# ch.net
KiCad netlist of a schematic drawn in Altium Designer
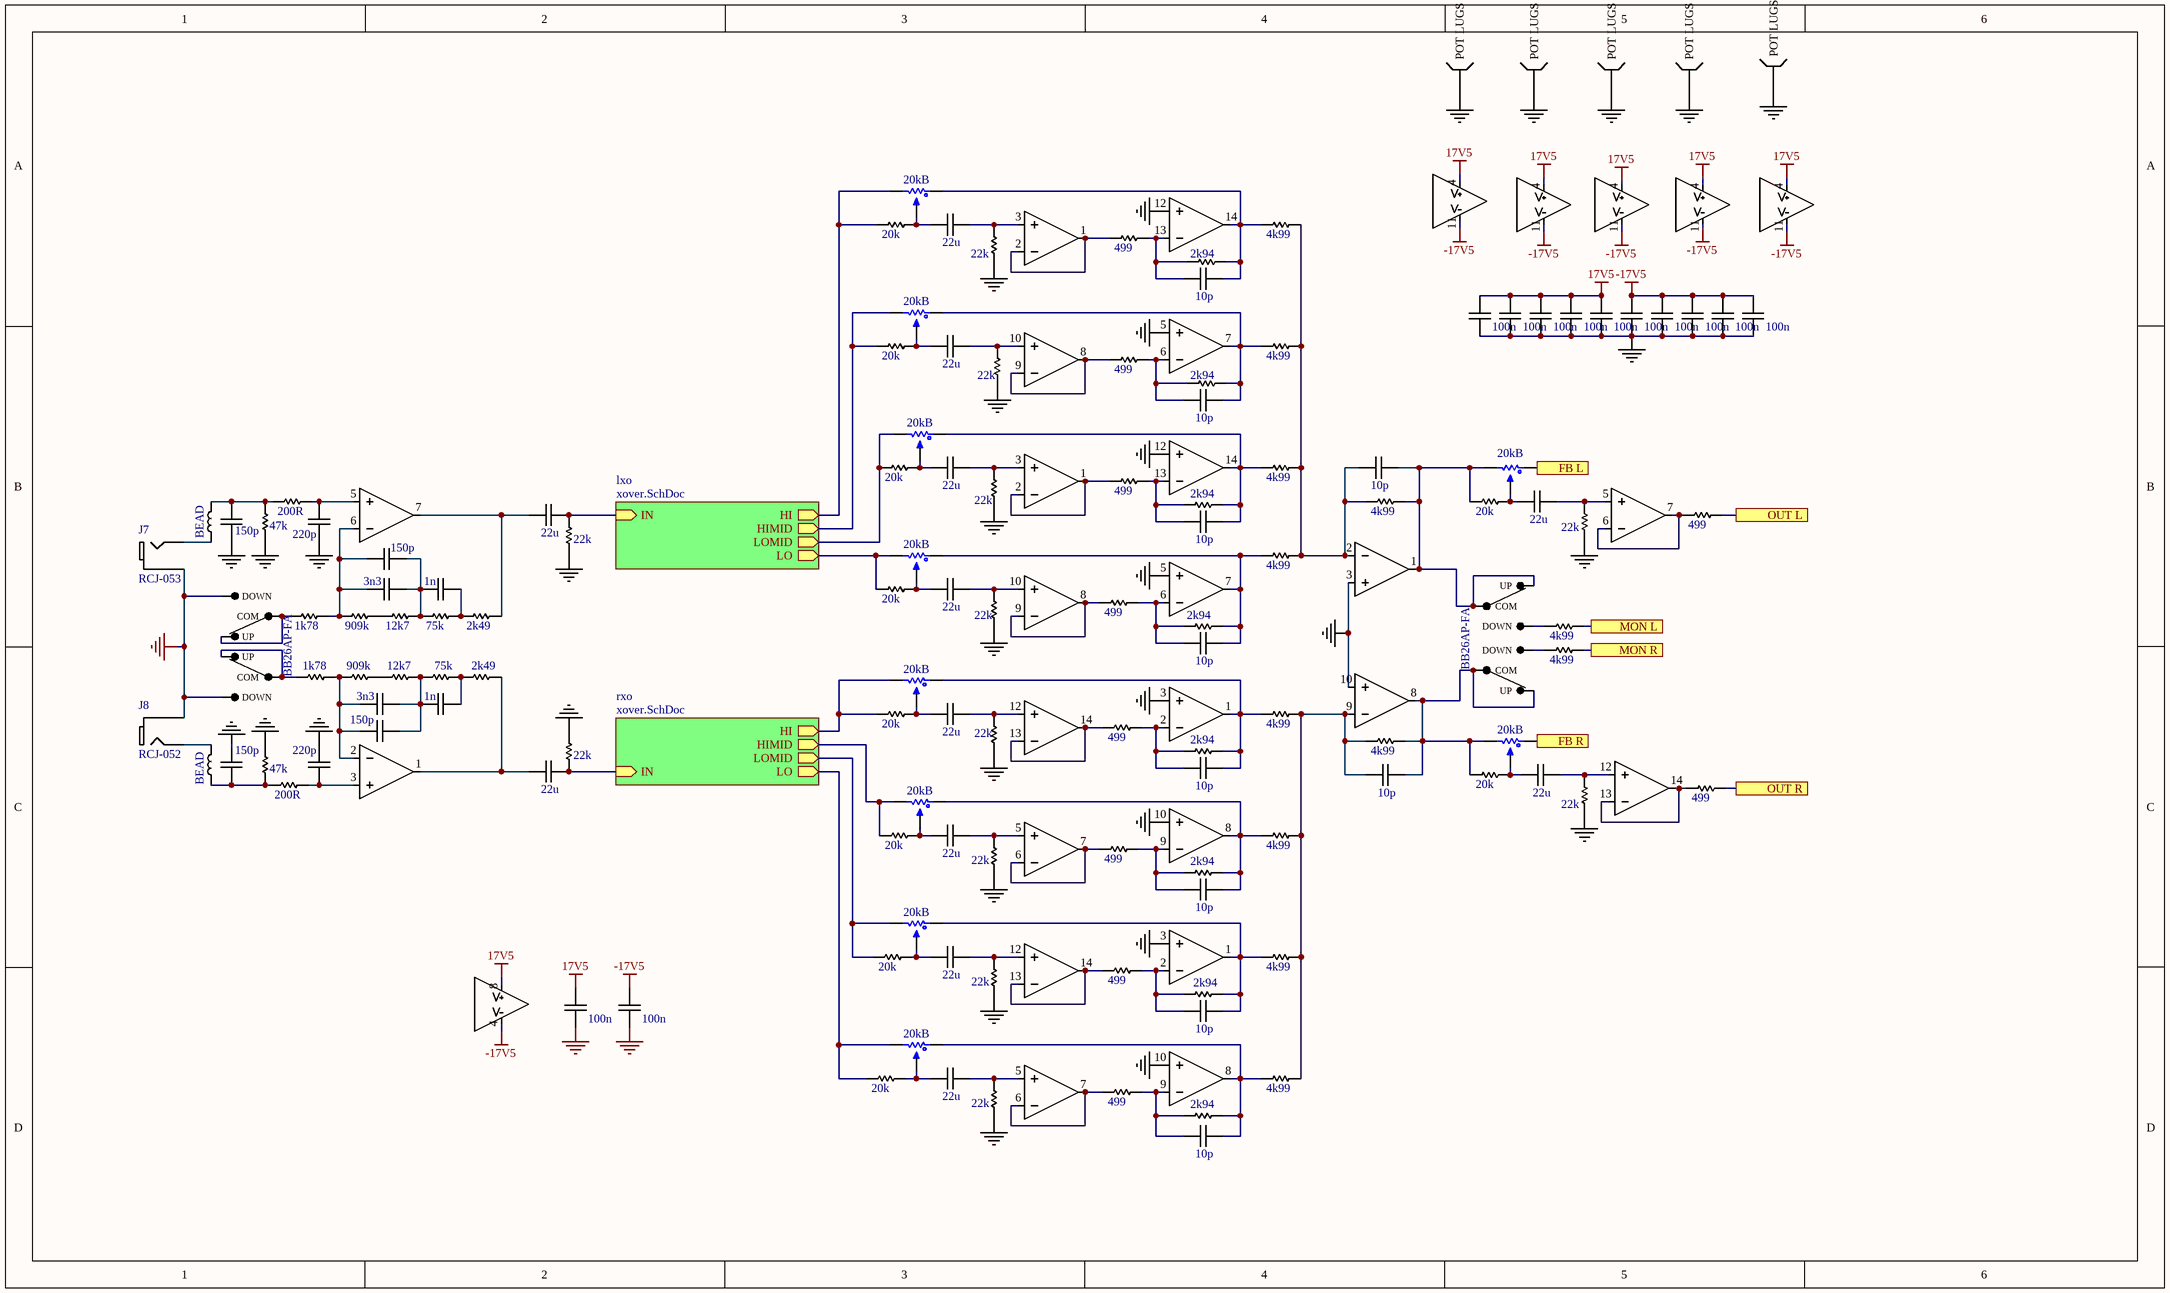
[diagram p0: ch.SchDoc]

(export (version "E")
  (design (tool "Eeschema 10.0.6"))
  (components
    (comp (ref "C1")
      (value "22u")
      (footprint "0805")
      (fields (field (name "PARTNUMBER") "GRT21BR61E226ME13L"))
      (libsource (lib "mix") (part "CAP"))
    )
    (comp (ref "C2")
      (value "10p")
      (footprint "0805")
      (fields (field (name "PARTNUMBER") "CC0805JRNPO9BN100"))
      (libsource (lib "mix") (part "CAP"))
    )
    (comp (ref "C3")
      (value "100n")
      (footprint "0805")
      (fields (field (name "PARTNUMBER") "C0805C104K1RAC7800"))
      (libsource (lib "mix") (part "CAP"))
    )
    (comp (ref "C4")
      (value "100n")
      (footprint "0805")
      (fields (field (name "PARTNUMBER") "C0805C104K1RAC7800"))
      (libsource (lib "mix") (part "CAP"))
    )
    (comp (ref "C6")
      (value "100n")
      (footprint "0805")
      (fields (field (name "PARTNUMBER") "C0805C104K1RAC7800"))
      (libsource (lib "mix") (part "CAP"))
    )
    (comp (ref "C8")
      (value "100n")
      (footprint "0805")
      (fields (field (name "PARTNUMBER") "C0805C104K1RAC7800"))
      (libsource (lib "mix") (part "CAP"))
    )
    (comp (ref "C9")
      (value "100n")
      (footprint "0805")
      (fields (field (name "PARTNUMBER") "C0805C104K1RAC7800"))
      (libsource (lib "mix") (part "CAP"))
    )
    (comp (ref "C10")
      (value "22u")
      (footprint "0805")
      (fields (field (name "PARTNUMBER") "GRT21BR61E226ME13L"))
      (libsource (lib "mix") (part "CAP"))
    )
    (comp (ref "C11")
      (value "10p")
      (footprint "0805")
      (fields (field (name "PARTNUMBER") "CC0805JRNPO9BN100"))
      (libsource (lib "mix") (part "CAP"))
    )
    (comp (ref "C12")
      (value "100n")
      (footprint "0805")
      (fields (field (name "PARTNUMBER") "C0805C104K1RAC7800"))
      (libsource (lib "mix") (part "CAP"))
    )
    (comp (ref "C13")
      (value "22u")
      (footprint "0805")
      (fields (field (name "PARTNUMBER") "GRT21BR61E226ME13L"))
      (libsource (lib "mix") (part "CAP"))
    )
    (comp (ref "C14")
      (value "22u")
      (footprint "0805")
      (fields (field (name "PARTNUMBER") "GRT21BR61E226ME13L"))
      (libsource (lib "mix") (part "CAP"))
    )
    (comp (ref "C16")
      (value "10p")
      (footprint "0805")
      (fields (field (name "PARTNUMBER") "CC0805JRNPO9BN100"))
      (libsource (lib "mix") (part "CAP"))
    )
    (comp (ref "C18")
      (value "22u")
      (footprint "0805")
      (fields (field (name "PARTNUMBER") "GRT21BR61E226ME13L"))
      (libsource (lib "mix") (part "CAP"))
    )
    (comp (ref "C19")
      (value "10p")
      (footprint "0805")
      (fields (field (name "PARTNUMBER") "CC0805JRNPO9BN100"))
      (libsource (lib "mix") (part "CAP"))
    )
    (comp (ref "C20")
      (value "22u")
      (footprint "0805")
      (fields (field (name "PARTNUMBER") "GRT21BR61E226ME13L"))
      (libsource (lib "mix") (part "CAP"))
    )
    (comp (ref "C21")
      (value "10p")
      (footprint "0805")
      (fields (field (name "PARTNUMBER") "CC0805JRNPO9BN100"))
      (libsource (lib "mix") (part "CAP"))
    )
    (comp (ref "C22")
      (value "22u")
      (footprint "0805")
      (fields (field (name "PARTNUMBER") "GRT21BR61E226ME13L"))
      (libsource (lib "mix") (part "CAP"))
    )
    (comp (ref "C25")
      (value "22u")
      (footprint "0805")
      (fields (field (name "PARTNUMBER") "GRT21BR61E226ME13L"))
      (libsource (lib "mix") (part "CAP"))
    )
    (comp (ref "C27")
      (value "10p")
      (footprint "0805")
      (fields (field (name "PARTNUMBER") "CC0805JRNPO9BN100"))
      (libsource (lib "mix") (part "CAP"))
    )
    (comp (ref "C28")
      (value "10p")
      (footprint "0805")
      (fields (field (name "PARTNUMBER") "CC0805JRNPO9BN100"))
      (libsource (lib "mix") (part "CAP"))
    )
    (comp (ref "C29")
      (value "22u")
      (footprint "0805")
      (fields (field (name "PARTNUMBER") "GRT21BR61E226ME13L"))
      (libsource (lib "mix") (part "CAP"))
    )
    (comp (ref "C32")
      (value "10p")
      (footprint "0805")
      (fields (field (name "PARTNUMBER") "CC0805JRNPO9BN100"))
      (libsource (lib "mix") (part "CAP"))
    )
    (comp (ref "C34")
      (value "22u")
      (footprint "0805")
      (fields (field (name "PARTNUMBER") "GRT21BR61E226ME13L"))
      (libsource (lib "mix") (part "CAP"))
    )
    (comp (ref "C35")
      (value "10p")
      (footprint "0805")
      (fields (field (name "PARTNUMBER") "CC0805JRNPO9BN100"))
      (libsource (lib "mix") (part "CAP"))
    )
    (comp (ref "C42")
      (value "10p")
      (footprint "0805")
      (fields (field (name "PARTNUMBER") "CC0805JRNPO9BN100"))
      (libsource (lib "mix") (part "CAP"))
    )
    (comp (ref "C63")
      (value "220p")
      (footprint "0805")
      (fields (field (name "PARTNUMBER") "C0805C221J1GACTU"))
      (libsource (lib "mix") (part "CAP"))
    )
    (comp (ref "C64")
      (value "150p")
      (footprint "0805")
      (fields (field (name "PARTNUMBER") "08055A151FAT2A"))
      (libsource (lib "mix") (part "CAP"))
    )
    (comp (ref "C65")
      (value "22u")
      (footprint "0805")
      (fields (field (name "PARTNUMBER") "GRT21BR61E226ME13L"))
      (libsource (lib "mix") (part "CAP"))
    )
    (comp (ref "C67")
      (value "150p")
      (footprint "0805")
      (fields (field (name "PARTNUMBER") "08055A151FAT2A"))
      (libsource (lib "mix") (part "CAP"))
    )
    (comp (ref "C68")
      (value "3n3")
      (footprint "0805")
      (fields (field (name "PARTNUMBER") "GRM2165C1H332FA01D"))
      (libsource (lib "mix") (part "CAP"))
    )
    (comp (ref "C69")
      (value "1n")
      (footprint "0805")
      (fields (field (name "PARTNUMBER") "GRM2165C1H102FA01J"))
      (libsource (lib "mix") (part "CAP"))
    )
    (comp (ref "C71")
      (value "100n")
      (footprint "0805")
      (fields (field (name "PARTNUMBER") "C0805C104K1RAC7800"))
      (libsource (lib "mix") (part "CAP"))
    )
    (comp (ref "C72")
      (value "100n")
      (footprint "0805")
      (fields (field (name "PARTNUMBER") "C0805C104K1RAC7800"))
      (libsource (lib "mix") (part "CAP"))
    )
    (comp (ref "C74")
      (value "3n3")
      (footprint "0805")
      (fields (field (name "PARTNUMBER") "GRM2165C1H332FA01D"))
      (libsource (lib "mix") (part "CAP"))
    )
    (comp (ref "C75")
      (value "1n")
      (footprint "0805")
      (fields (field (name "PARTNUMBER") "GRM2165C1H102FA01J"))
      (libsource (lib "mix") (part "CAP"))
    )
    (comp (ref "C76")
      (value "150p")
      (footprint "0805")
      (fields (field (name "PARTNUMBER") "08055A151FAT2A"))
      (libsource (lib "mix") (part "CAP"))
    )
    (comp (ref "C78")
      (value "150p")
      (footprint "0805")
      (fields (field (name "PARTNUMBER") "08055A151FAT2A"))
      (libsource (lib "mix") (part "CAP"))
    )
    (comp (ref "C79")
      (value "22u")
      (footprint "0805")
      (fields (field (name "PARTNUMBER") "GRT21BR61E226ME13L"))
      (libsource (lib "mix") (part "CAP"))
    )
    (comp (ref "C80")
      (value "220p")
      (footprint "0805")
      (fields (field (name "PARTNUMBER") "C0805C221J1GACTU"))
      (libsource (lib "mix") (part "CAP"))
    )
    (comp (ref "C203")
      (value "100n")
      (footprint "0805")
      (fields (field (name "PARTNUMBER") "C0805C104K1RAC7800"))
      (libsource (lib "mix") (part "CAP"))
    )
    (comp (ref "C208")
      (value "100n")
      (footprint "0805")
      (fields (field (name "PARTNUMBER") "C0805C104K1RAC7800"))
      (libsource (lib "mix") (part "CAP"))
    )
    (comp (ref "C210")
      (value "100n")
      (footprint "0805")
      (fields (field (name "PARTNUMBER") "C0805C104K1RAC7800"))
      (libsource (lib "mix") (part "CAP"))
    )
    (comp (ref "C215")
      (value "100n")
      (footprint "0805")
      (fields (field (name "PARTNUMBER") "C0805C104K1RAC7800"))
      (libsource (lib "mix") (part "CAP"))
    )
    (comp (ref "J7") (value "RCJ-053") (footprint "RCJ-053") (libsource (lib "mix") (part "RCJ-053")))
    (comp (ref "J8") (value "RCJ-052") (footprint "RCJ-052") (libsource (lib "mix") (part "RCJ-052")))
    (comp (ref "L1")
      (value "BEAD")
      (footprint "0805")
      (fields (field (name "PARTNUMBER") "BLM21PG121SH1D"))
      (libsource (lib "mix") (part "BLM21PG121SH1D"))
    )
    (comp (ref "L2")
      (value "BEAD")
      (footprint "0805")
      (fields (field (name "PARTNUMBER") "BLM21PG121SH1D"))
      (libsource (lib "mix") (part "BLM21PG121SH1D"))
    )
    (comp (ref "R1")
      (value "20kB")
      (footprint "P0925N-FC15AR10K")
      (description "P0925N-FC15BR20K")
      (libsource (lib "") (part "P0925N-FC15BR20K_1"))
    )
    (comp (ref "R2")
      (value "499")
      (footprint "0805")
      (fields (field (name "PARTNUMBER") "ERJ-6ENF4990V"))
      (libsource (lib "mix") (part "RES"))
    )
    (comp (ref "R3")
      (value "22k")
      (footprint "0805")
      (fields (field (name "PARTNUMBER") "ERJ-6ENF2202V"))
      (libsource (lib "mix") (part "RES"))
    )
    (comp (ref "R4")
      (value "2k94")
      (footprint "0805")
      (fields (field (name "PARTNUMBER") "ERJ-6ENF2941V"))
      (libsource (lib "mix") (part "RES"))
    )
    (comp (ref "R8")
      (value "499")
      (footprint "0805")
      (fields (field (name "PARTNUMBER") "ERJ-6ENF4990V"))
      (libsource (lib "mix") (part "RES"))
    )
    (comp (ref "R9")
      (value "22k")
      (footprint "0805")
      (fields (field (name "PARTNUMBER") "ERJ-6ENF2202V"))
      (libsource (lib "mix") (part "RES"))
    )
    (comp (ref "R10")
      (value "2k94")
      (footprint "0805")
      (fields (field (name "PARTNUMBER") "ERJ-6ENF2941V"))
      (libsource (lib "mix") (part "RES"))
    )
    (comp (ref "R11")
      (value "499")
      (footprint "0805")
      (fields (field (name "PARTNUMBER") "ERJ-6ENF4990V"))
      (libsource (lib "mix") (part "RES"))
    )
    (comp (ref "R12")
      (value "22k")
      (footprint "0805")
      (fields (field (name "PARTNUMBER") "ERJ-6ENF2202V"))
      (libsource (lib "mix") (part "RES"))
    )
    (comp (ref "R14")
      (value "4k99")
      (footprint "0805")
      (fields (field (name "PARTNUMBER") "ERJ-6ENF4991V"))
      (libsource (lib "mix") (part "RES"))
    )
    (comp (ref "R15")
      (value "499")
      (footprint "0805")
      (fields (field (name "PARTNUMBER") "ERJ-6ENF4990V"))
      (libsource (lib "mix") (part "RES"))
    )
    (comp (ref "R16")
      (value "20k")
      (footprint "0805")
      (fields (field (name "PARTNUMBER") "ERJ-6ENF2002V"))
      (libsource (lib "mix") (part "RES"))
    )
    (comp (ref "R17")
      (value "2k94")
      (footprint "0805")
      (fields (field (name "PARTNUMBER") "ERJ-6ENF2941V"))
      (libsource (lib "mix") (part "RES"))
    )
    (comp (ref "R18")
      (value "20k")
      (footprint "0805")
      (fields (field (name "PARTNUMBER") "ERJ-6ENF2002V"))
      (libsource (lib "mix") (part "RES"))
    )
    (comp (ref "R19")
      (value "22k")
      (footprint "0805")
      (fields (field (name "PARTNUMBER") "ERJ-6ENF2202V"))
      (libsource (lib "mix") (part "RES"))
    )
    (comp (ref "R20")
      (value "4k99")
      (footprint "0805")
      (fields (field (name "PARTNUMBER") "ERJ-6ENF4991V"))
      (libsource (lib "mix") (part "RES"))
    )
    (comp (ref "R21")
      (value "4k99")
      (footprint "0805")
      (fields (field (name "PARTNUMBER") "ERJ-6ENF4991V"))
      (libsource (lib "mix") (part "RES"))
    )
    (comp (ref "R22")
      (value "499")
      (footprint "0805")
      (fields (field (name "PARTNUMBER") "ERJ-6ENF4990V"))
      (libsource (lib "mix") (part "RES"))
    )
    (comp (ref "R23")
      (value "22k")
      (footprint "0805")
      (fields (field (name "PARTNUMBER") "ERJ-6ENF2202V"))
      (libsource (lib "mix") (part "RES"))
    )
    (comp (ref "R24")
      (value "2k94")
      (footprint "0805")
      (fields (field (name "PARTNUMBER") "ERJ-6ENF2941V"))
      (libsource (lib "mix") (part "RES"))
    )
    (comp (ref "R25")
      (value "20k")
      (footprint "0805")
      (fields (field (name "PARTNUMBER") "ERJ-6ENF2002V"))
      (libsource (lib "mix") (part "RES"))
    )
    (comp (ref "R28")
      (value "499")
      (footprint "0805")
      (fields (field (name "PARTNUMBER") "ERJ-6ENF4990V"))
      (libsource (lib "mix") (part "RES"))
    )
    (comp (ref "R33")
      (value "22k")
      (footprint "0805")
      (fields (field (name "PARTNUMBER") "ERJ-6ENF2202V"))
      (libsource (lib "mix") (part "RES"))
    )
    (comp (ref "R34")
      (value "2k94")
      (footprint "0805")
      (fields (field (name "PARTNUMBER") "ERJ-6ENF2941V"))
      (libsource (lib "mix") (part "RES"))
    )
    (comp (ref "R35")
      (value "20k")
      (footprint "0805")
      (fields (field (name "PARTNUMBER") "ERJ-6ENF2002V"))
      (libsource (lib "mix") (part "RES"))
    )
    (comp (ref "R36")
      (value "499")
      (footprint "0805")
      (fields (field (name "PARTNUMBER") "ERJ-6ENF4990V"))
      (libsource (lib "mix") (part "RES"))
    )
    (comp (ref "R37")
      (value "22k")
      (footprint "0805")
      (fields (field (name "PARTNUMBER") "ERJ-6ENF2202V"))
      (libsource (lib "mix") (part "RES"))
    )
    (comp (ref "R38")
      (value "499")
      (footprint "0805")
      (fields (field (name "PARTNUMBER") "ERJ-6ENF4990V"))
      (libsource (lib "mix") (part "RES"))
    )
    (comp (ref "R39")
      (value "22k")
      (footprint "0805")
      (fields (field (name "PARTNUMBER") "ERJ-6ENF2202V"))
      (libsource (lib "mix") (part "RES"))
    )
    (comp (ref "R40")
      (value "2k94")
      (footprint "0805")
      (fields (field (name "PARTNUMBER") "ERJ-6ENF2941V"))
      (libsource (lib "mix") (part "RES"))
    )
    (comp (ref "R41")
      (value "499")
      (footprint "0805")
      (fields (field (name "PARTNUMBER") "ERJ-6ENF4990V"))
      (libsource (lib "mix") (part "RES"))
    )
    (comp (ref "R42")
      (value "22k")
      (footprint "0805")
      (fields (field (name "PARTNUMBER") "ERJ-6ENF2202V"))
      (libsource (lib "mix") (part "RES"))
    )
    (comp (ref "R43")
      (value "2k94")
      (footprint "0805")
      (fields (field (name "PARTNUMBER") "ERJ-6ENF2941V"))
      (libsource (lib "mix") (part "RES"))
    )
    (comp (ref "R44")
      (value "499")
      (footprint "0805")
      (fields (field (name "PARTNUMBER") "ERJ-6ENF4990V"))
      (libsource (lib "mix") (part "RES"))
    )
    (comp (ref "R45")
      (value "22k")
      (footprint "0805")
      (fields (field (name "PARTNUMBER") "ERJ-6ENF2202V"))
      (libsource (lib "mix") (part "RES"))
    )
    (comp (ref "R46")
      (value "2k94")
      (footprint "0805")
      (fields (field (name "PARTNUMBER") "ERJ-6ENF2941V"))
      (libsource (lib "mix") (part "RES"))
    )
    (comp (ref "R52")
      (value "20k")
      (footprint "0805")
      (fields (field (name "PARTNUMBER") "ERJ-6ENF2002V"))
      (libsource (lib "mix") (part "RES"))
    )
    (comp (ref "R53")
      (value "200R")
      (footprint "0805")
      (fields (field (name "PARTNUMBER") "ERJ-6ENF2000V"))
      (libsource (lib "mix") (part "RES"))
    )
    (comp (ref "R54")
      (value "22k")
      (footprint "0805")
      (fields (field (name "PARTNUMBER") "ERJ-6ENF2202V"))
      (libsource (lib "mix") (part "RES"))
    )
    (comp (ref "R55")
      (value "47k")
      (footprint "0805")
      (fields (field (name "PARTNUMBER") "ERJ-6ENF4702V"))
      (libsource (lib "mix") (part "RES"))
    )
    (comp (ref "R56")
      (value "20k")
      (footprint "0805")
      (fields (field (name "PARTNUMBER") "ERJ-6ENF2002V"))
      (libsource (lib "mix") (part "RES"))
    )
    (comp (ref "R57")
      (value "909k")
      (footprint "0805")
      (fields (field (name "PARTNUMBER") "ERJ-PB6B9093V"))
      (libsource (lib "mix") (part "RES"))
    )
    (comp (ref "R58")
      (value "12k7")
      (footprint "0805")
      (fields (field (name "PARTNUMBER") "ERJ-PB6B1272V"))
      (libsource (lib "mix") (part "RES"))
    )
    (comp (ref "R59")
      (value "2k49")
      (footprint "0805")
      (fields (field (name "PARTNUMBER") "ERA6AEB2491V"))
      (libsource (lib "mix") (part "RES"))
    )
    (comp (ref "R60")
      (value "20k")
      (footprint "0805")
      (fields (field (name "PARTNUMBER") "ERJ-6ENF2002V"))
      (libsource (lib "mix") (part "RES"))
    )
    (comp (ref "R61")
      (value "20k")
      (footprint "0805")
      (fields (field (name "PARTNUMBER") "ERJ-6ENF2002V"))
      (libsource (lib "mix") (part "RES"))
    )
    (comp (ref "R62")
      (value "1k78")
      (footprint "0805")
      (fields (field (name "PARTNUMBER") "ERJ-PB6B1781V"))
      (libsource (lib "mix") (part "RES"))
    )
    (comp (ref "R63")
      (value "75k")
      (footprint "0805")
      (fields (field (name "PARTNUMBER") "ERA6AEB753V"))
      (libsource (lib "mix") (part "RES"))
    )
    (comp (ref "R64")
      (value "20k")
      (footprint "0805")
      (fields (field (name "PARTNUMBER") "ERJ-6ENF2002V"))
      (libsource (lib "mix") (part "RES"))
    )
    (comp (ref "R65")
      (value "20k")
      (footprint "0805")
      (fields (field (name "PARTNUMBER") "ERJ-6ENF2002V"))
      (libsource (lib "mix") (part "RES"))
    )
    (comp (ref "R66")
      (value "909k")
      (footprint "0805")
      (fields (field (name "PARTNUMBER") "ERJ-PB6B9093V"))
      (libsource (lib "mix") (part "RES"))
    )
    (comp (ref "R67")
      (value "12k7")
      (footprint "0805")
      (fields (field (name "PARTNUMBER") "ERJ-PB6B1272V"))
      (libsource (lib "mix") (part "RES"))
    )
    (comp (ref "R68")
      (value "1k78")
      (footprint "0805")
      (fields (field (name "PARTNUMBER") "ERJ-PB6B1781V"))
      (libsource (lib "mix") (part "RES"))
    )
    (comp (ref "R69")
      (value "75k")
      (footprint "0805")
      (fields (field (name "PARTNUMBER") "ERA6AEB753V"))
      (libsource (lib "mix") (part "RES"))
    )
    (comp (ref "R70")
      (value "2k49")
      (footprint "0805")
      (fields (field (name "PARTNUMBER") "ERA6AEB2491V"))
      (libsource (lib "mix") (part "RES"))
    )
    (comp (ref "R72")
      (value "47k")
      (footprint "0805")
      (fields (field (name "PARTNUMBER") "ERJ-6ENF4702V"))
      (libsource (lib "mix") (part "RES"))
    )
    (comp (ref "R73")
      (value "22k")
      (footprint "0805")
      (fields (field (name "PARTNUMBER") "ERJ-6ENF2202V"))
      (libsource (lib "mix") (part "RES"))
    )
    (comp (ref "R74")
      (value "200R")
      (footprint "0805")
      (fields (field (name "PARTNUMBER") "ERJ-6ENF2000V"))
      (libsource (lib "mix") (part "RES"))
    )
    (comp (ref "R75")
      (value "4k99")
      (footprint "0805")
      (fields (field (name "PARTNUMBER") "ERJ-6ENF4991V"))
      (libsource (lib "mix") (part "RES"))
    )
    (comp (ref "R76")
      (value "4k99")
      (footprint "0805")
      (fields (field (name "PARTNUMBER") "ERJ-6ENF4991V"))
      (libsource (lib "mix") (part "RES"))
    )
    (comp (ref "R148")
      (value "20kB")
      (footprint "P0925N-FC15AR10K")
      (description "P0925N-FC15BR20K")
      (libsource (lib "") (part "P0925N-FC15BR20K_1"))
    )
    (comp (ref "R149")
      (value "20kB")
      (footprint "P0925N-FC15AR10K")
      (description "P0925N-FC15BR20K")
      (libsource (lib "mix") (part "P0925N-FC15BR20K"))
    )
    (comp (ref "R150")
      (value "20kB")
      (footprint "P0925N-FC15AR10K")
      (description "P0925N-FC15BR20K")
      (libsource (lib "") (part "P0925N-FC15BR20K_2"))
    )
    (comp (ref "R151")
      (value "20kB")
      (footprint "P0925N-FC15AR10K")
      (description "P0925N-FC15BR20K")
      (libsource (lib "") (part "P0925N-FC15BR20K_1"))
    )
    (comp (ref "R173")
      (value "4k99")
      (footprint "0805")
      (fields (field (name "PARTNUMBER") "ERJ-6ENF4991V"))
      (libsource (lib "mix") (part "RES"))
    )
    (comp (ref "R177")
      (value "4k99")
      (footprint "0805")
      (fields (field (name "PARTNUMBER") "ERJ-6ENF4991V"))
      (libsource (lib "mix") (part "RES"))
    )
    (comp (ref "R184")
      (value "4k99")
      (footprint "0805")
      (fields (field (name "PARTNUMBER") "ERJ-6ENF4991V"))
      (libsource (lib "mix") (part "RES"))
    )
    (comp (ref "R187")
      (value "4k99")
      (footprint "0805")
      (fields (field (name "PARTNUMBER") "ERJ-6ENF4991V"))
      (libsource (lib "mix") (part "RES"))
    )
    (comp (ref "R200")
      (value "4k99")
      (footprint "0805")
      (fields (field (name "PARTNUMBER") "ERJ-6ENF4991V"))
      (libsource (lib "mix") (part "RES"))
    )
    (comp (ref "R201")
      (value "4k99")
      (footprint "0805")
      (fields (field (name "PARTNUMBER") "ERJ-6ENF4991V"))
      (libsource (lib "mix") (part "RES"))
    )
    (comp (ref "R207")
      (value "4k99")
      (footprint "0805")
      (fields (field (name "PARTNUMBER") "ERJ-6ENF4991V"))
      (libsource (lib "mix") (part "RES"))
    )
    (comp (ref "SW1") (value "BB26AP-FA") (footprint "BB26AP-FA") (libsource (lib "mix") (part "BB26AP-FA")))
    (comp (ref "SW5") (value "BB26AP-FA") (footprint "BB26AP-FA") (libsource (lib "mix") (part "BB26AP-FA")))
    (comp (ref "U1")
      (value "OPA16X4")
      (footprint "SOIC127P600X175-14M")
      (fields (field (name "PARTNUMBER") "OPA1664AIDR"))
      (libsource (lib "mix") (part "OPA16X4"))
    )
    (comp (ref "U2")
      (value "OPA16X4")
      (footprint "SOIC127P600X175-14M")
      (fields (field (name "PARTNUMBER") "OPA1664AIDR"))
      (libsource (lib "mix") (part "OPA16X4"))
    )
    (comp (ref "U3")
      (value "OPA16X4")
      (footprint "SOIC127P600X175-14M")
      (fields (field (name "PARTNUMBER") "OPA1664AIDR"))
      (libsource (lib "mix") (part "OPA16X4"))
    )
    (comp (ref "U4")
      (value "OPA16X4")
      (footprint "SOIC127P600X175-14M")
      (fields (field (name "PARTNUMBER") "OPA1664AIDR"))
      (libsource (lib "mix") (part "OPA16X4"))
    )
    (comp (ref "U5")
      (value "OPA16X4")
      (footprint "SOIC127P600X175-14M")
      (fields (field (name "PARTNUMBER") "OPA1664AIDR"))
      (libsource (lib "mix") (part "OPA16X4"))
    )
    (comp (ref "U20")
      (value "OPA16X2")
      (footprint "SOIC127P600X175-8M")
      (fields (field (name "PARTNUMBER") "OPA1662AIDRQ1"))
      (libsource (lib "") (part "OPA16X2_1"))
    )
  )
  (nets
    (net (code "1") (name "-17V5") (class "Default")
      (node (ref "C12") (pin "1") (pinfunction "1_1") (pintype "passive"))
      (node (ref "C210") (pin "1") (pinfunction "1_1") (pintype "passive"))
      (node (ref "C215") (pin "1") (pinfunction "1_1") (pintype "passive"))
      (node (ref "C6") (pin "1") (pinfunction "1_1") (pintype "passive"))
      (node (ref "C72") (pin "1") (pinfunction "1_1") (pintype "passive"))
      (node (ref "C8") (pin "1") (pinfunction "1_1") (pintype "passive"))
      (node (ref "U1") (pin "11") (pinfunction "V-_11") (pintype "passive"))
      (node (ref "U2") (pin "11") (pinfunction "V-_11") (pintype "passive"))
      (node (ref "U20") (pin "4") (pinfunction "V-_4") (pintype "passive"))
      (node (ref "U3") (pin "11") (pinfunction "V-_11") (pintype "passive"))
      (node (ref "U4") (pin "11") (pinfunction "V-_11") (pintype "passive"))
      (node (ref "U5") (pin "11") (pinfunction "V-_11") (pintype "passive"))
    )
    (net (code "2") (name "/FB L") (class "Default")
      (node (ref "R1") (pin "1") (pinfunction "1_1") (pintype "passive"))
    )
    (net (code "3") (name "/FB R") (class "Default")
      (node (ref "R1") (pin "4") (pinfunction "4_4") (pintype "passive"))
    )
    (net (code "4") (name "/HI") (class "Default")
      (node (ref "R148") (pin "6") (pinfunction "6_6") (pintype "passive"))
      (node (ref "R56") (pin "2") (pinfunction "2_2") (pintype "passive"))
    )
    (net (code "5") (name "/HIMID") (class "Default")
      (node (ref "R149") (pin "6") (pinfunction "6_6") (pintype "passive"))
      (node (ref "R61") (pin "2") (pinfunction "2_2") (pintype "passive"))
    )
    (net (code "6") (name "/HIMID_1") (class "Default")
      (node (ref "R149") (pin "3") (pinfunction "3_3") (pintype "passive"))
      (node (ref "R18") (pin "2") (pinfunction "2_2") (pintype "passive"))
    )
    (net (code "7") (name "/HI_1") (class "Default")
      (node (ref "R148") (pin "3") (pinfunction "3_3") (pintype "passive"))
      (node (ref "R16") (pin "2") (pinfunction "2_2") (pintype "passive"))
    )
    (net (code "8") (name "/IN") (class "Default")
      (node (ref "C79") (pin "2") (pinfunction "2_2") (pintype "passive"))
      (node (ref "R73") (pin "2") (pinfunction "2_2") (pintype "passive"))
    )
    (net (code "9") (name "/IN_1") (class "Default")
      (node (ref "C65") (pin "2") (pinfunction "2_2") (pintype "passive"))
      (node (ref "R54") (pin "1") (pinfunction "1_1") (pintype "passive"))
    )
    (net (code "10") (name "/LO") (class "Default")
      (node (ref "R151") (pin "6") (pinfunction "6_6") (pintype "passive"))
      (node (ref "R65") (pin "2") (pinfunction "2_2") (pintype "passive"))
    )
    (net (code "11") (name "/LOMID") (class "Default")
      (node (ref "R150") (pin "6") (pinfunction "6_6") (pintype "passive"))
      (node (ref "R64") (pin "2") (pinfunction "2_2") (pintype "passive"))
    )
    (net (code "12") (name "/LOMID_1") (class "Default")
      (node (ref "R150") (pin "3") (pinfunction "3_3") (pintype "passive"))
      (node (ref "R25") (pin "2") (pinfunction "2_2") (pintype "passive"))
    )
    (net (code "13") (name "/LO_1") (class "Default")
      (node (ref "R151") (pin "3") (pinfunction "3_3") (pintype "passive"))
      (node (ref "R52") (pin "2") (pinfunction "2_2") (pintype "passive"))
    )
    (net (code "14") (name "/MON L") (class "Default")
      (node (ref "R75") (pin "2") (pinfunction "2_2") (pintype "passive"))
    )
    (net (code "15") (name "/MON R") (class "Default")
      (node (ref "R76") (pin "2") (pinfunction "2_2") (pintype "passive"))
    )
    (net (code "16") (name "/OUT L") (class "Default")
      (node (ref "R15") (pin "2") (pinfunction "2_2") (pintype "passive"))
    )
    (net (code "17") (name "/OUT R") (class "Default")
      (node (ref "R36") (pin "2") (pinfunction "2_2") (pintype "passive"))
    )
    (net (code "18") (name "17V5") (class "Default")
      (node (ref "C203") (pin "1") (pinfunction "1_1") (pintype "passive"))
      (node (ref "C208") (pin "1") (pinfunction "1_1") (pintype "passive"))
      (node (ref "C3") (pin "1") (pinfunction "1_1") (pintype "passive"))
      (node (ref "C4") (pin "1") (pinfunction "1_1") (pintype "passive"))
      (node (ref "C71") (pin "1") (pinfunction "1_1") (pintype "passive"))
      (node (ref "C9") (pin "1") (pinfunction "1_1") (pintype "passive"))
      (node (ref "U1") (pin "4") (pinfunction "V+_4") (pintype "passive"))
      (node (ref "U2") (pin "4") (pinfunction "V+_4") (pintype "passive"))
      (node (ref "U20") (pin "8") (pinfunction "V+_8") (pintype "passive"))
      (node (ref "U3") (pin "4") (pinfunction "V+_4") (pintype "passive"))
      (node (ref "U4") (pin "4") (pinfunction "V+_4") (pintype "passive"))
      (node (ref "U5") (pin "4") (pinfunction "V+_4") (pintype "passive"))
    )
    (net (code "19") (name "GND") (class "Default")
      (node (ref "C12") (pin "2") (pinfunction "2_2") (pintype "passive"))
      (node (ref "C203") (pin "2") (pinfunction "2_2") (pintype "passive"))
      (node (ref "C208") (pin "2") (pinfunction "2_2") (pintype "passive"))
      (node (ref "C210") (pin "2") (pinfunction "2_2") (pintype "passive"))
      (node (ref "C215") (pin "2") (pinfunction "2_2") (pintype "passive"))
      (node (ref "C3") (pin "2") (pinfunction "2_2") (pintype "passive"))
      (node (ref "C4") (pin "2") (pinfunction "2_2") (pintype "passive"))
      (node (ref "C6") (pin "2") (pinfunction "2_2") (pintype "passive"))
      (node (ref "C63") (pin "1") (pinfunction "1_1") (pintype "passive"))
      (node (ref "C64") (pin "1") (pinfunction "1_1") (pintype "passive"))
      (node (ref "C71") (pin "2") (pinfunction "2_2") (pintype "passive"))
      (node (ref "C72") (pin "2") (pinfunction "2_2") (pintype "passive"))
      (node (ref "C78") (pin "2") (pinfunction "2_2") (pintype "passive"))
      (node (ref "C8") (pin "2") (pinfunction "2_2") (pintype "passive"))
      (node (ref "C80") (pin "2") (pinfunction "2_2") (pintype "passive"))
      (node (ref "C9") (pin "2") (pinfunction "2_2") (pintype "passive"))
      (node (ref "J7") (pin "1") (pinfunction "1_1") (pintype "passive"))
      (node (ref "J8") (pin "1") (pinfunction "1_1") (pintype "passive"))
      (node (ref "R1") (pin "7") (pinfunction "POT_LUGS_7") (pintype "passive"))
      (node (ref "R12") (pin "1") (pinfunction "1_1") (pintype "passive"))
      (node (ref "R148") (pin "7") (pinfunction "POT_LUGS_7") (pintype "passive"))
      (node (ref "R149") (pin "7") (pinfunction "POT_LUGS_7") (pintype "passive"))
      (node (ref "R150") (pin "7") (pinfunction "POT_LUGS_7") (pintype "passive"))
      (node (ref "R151") (pin "7") (pinfunction "POT_LUGS_7") (pintype "passive"))
      (node (ref "R19") (pin "1") (pinfunction "1_1") (pintype "passive"))
      (node (ref "R23") (pin "1") (pinfunction "1_1") (pintype "passive"))
      (node (ref "R3") (pin "1") (pinfunction "1_1") (pintype "passive"))
      (node (ref "R33") (pin "1") (pinfunction "1_1") (pintype "passive"))
      (node (ref "R37") (pin "1") (pinfunction "1_1") (pintype "passive"))
      (node (ref "R39") (pin "1") (pinfunction "1_1") (pintype "passive"))
      (node (ref "R42") (pin "1") (pinfunction "1_1") (pintype "passive"))
      (node (ref "R45") (pin "1") (pinfunction "1_1") (pintype "passive"))
      (node (ref "R54") (pin "2") (pinfunction "2_2") (pintype "passive"))
      (node (ref "R55") (pin "1") (pinfunction "1_1") (pintype "passive"))
      (node (ref "R72") (pin "2") (pinfunction "2_2") (pintype "passive"))
      (node (ref "R73") (pin "1") (pinfunction "1_1") (pintype "passive"))
      (node (ref "R9") (pin "1") (pinfunction "1_1") (pintype "passive"))
      (node (ref "SW5") (pin "1") (pinfunction "DOWN_1") (pintype "passive"))
      (node (ref "SW5") (pin "4") (pinfunction "DOWN_4") (pintype "passive"))
      (node (ref "U1") (pin "12") (pinfunction "IN_D+_12") (pintype "passive"))
      (node (ref "U1") (pin "5") (pinfunction "IN_B+_5") (pintype "passive"))
      (node (ref "U2") (pin "12") (pinfunction "IN_D+_12") (pintype "passive"))
      (node (ref "U2") (pin "5") (pinfunction "IN_B+_5") (pintype "passive"))
      (node (ref "U3") (pin "10") (pinfunction "IN_C+_10") (pintype "passive"))
      (node (ref "U3") (pin "3") (pinfunction "+IN_A_3") (pintype "passive"))
      (node (ref "U4") (pin "10") (pinfunction "IN_C+_10") (pintype "passive"))
      (node (ref "U4") (pin "3") (pinfunction "+IN_A_3") (pintype "passive"))
      (node (ref "U5") (pin "10") (pinfunction "IN_C+_10") (pintype "passive"))
      (node (ref "U5") (pin "3") (pinfunction "+IN_A_3") (pintype "passive"))
    )
    (net (code "20") (name "Net-(C1-Pad1)") (class "Default")
      (node (ref "C1") (pin "1") (pinfunction "1_1") (pintype "passive"))
      (node (ref "R148") (pin "2") (pinfunction "2_2") (pintype "passive"))
      (node (ref "R16") (pin "1") (pinfunction "1_1") (pintype "passive"))
    )
    (net (code "21") (name "Net-(C10-Pad1)") (class "Default")
      (node (ref "C10") (pin "1") (pinfunction "1_1") (pintype "passive"))
      (node (ref "R149") (pin "2") (pinfunction "2_2") (pintype "passive"))
      (node (ref "R18") (pin "1") (pinfunction "1_1") (pintype "passive"))
    )
    (net (code "22") (name "Net-(C13-Pad1)") (class "Default")
      (node (ref "C13") (pin "1") (pinfunction "1_1") (pintype "passive"))
      (node (ref "R150") (pin "2") (pinfunction "2_2") (pintype "passive"))
      (node (ref "R25") (pin "1") (pinfunction "1_1") (pintype "passive"))
    )
    (net (code "23") (name "Net-(C14-Pad1)") (class "Default")
      (node (ref "C14") (pin "1") (pinfunction "1_1") (pintype "passive"))
      (node (ref "R1") (pin "2") (pinfunction "2_2") (pintype "passive"))
      (node (ref "R35") (pin "1") (pinfunction "1_1") (pintype "passive"))
    )
    (net (code "24") (name "Net-(C18-Pad1)") (class "Default")
      (node (ref "C18") (pin "1") (pinfunction "1_1") (pintype "passive"))
      (node (ref "R151") (pin "2") (pinfunction "2_2") (pintype "passive"))
      (node (ref "R52") (pin "1") (pinfunction "1_1") (pintype "passive"))
    )
    (net (code "25") (name "Net-(C20-Pad1)") (class "Default")
      (node (ref "C20") (pin "1") (pinfunction "1_1") (pintype "passive"))
      (node (ref "R148") (pin "5") (pinfunction "5_5") (pintype "passive"))
      (node (ref "R56") (pin "1") (pinfunction "1_1") (pintype "passive"))
    )
    (net (code "26") (name "Net-(C22-Pad1)") (class "Default")
      (node (ref "C22") (pin "1") (pinfunction "1_1") (pintype "passive"))
      (node (ref "R1") (pin "5") (pinfunction "5_5") (pintype "passive"))
      (node (ref "R60") (pin "1") (pinfunction "1_1") (pintype "passive"))
    )
    (net (code "27") (name "Net-(C25-Pad1)") (class "Default")
      (node (ref "C25") (pin "1") (pinfunction "1_1") (pintype "passive"))
      (node (ref "R149") (pin "5") (pinfunction "5_5") (pintype "passive"))
      (node (ref "R61") (pin "1") (pinfunction "1_1") (pintype "passive"))
    )
    (net (code "28") (name "Net-(C29-Pad1)") (class "Default")
      (node (ref "C29") (pin "1") (pinfunction "1_1") (pintype "passive"))
      (node (ref "R150") (pin "5") (pinfunction "5_5") (pintype "passive"))
      (node (ref "R64") (pin "1") (pinfunction "1_1") (pintype "passive"))
    )
    (net (code "29") (name "Net-(C34-Pad1)") (class "Default")
      (node (ref "C34") (pin "1") (pinfunction "1_1") (pintype "passive"))
      (node (ref "R151") (pin "5") (pinfunction "5_5") (pintype "passive"))
      (node (ref "R65") (pin "1") (pinfunction "1_1") (pintype "passive"))
    )
    (net (code "30") (name "Net-(C64-Pad2)") (class "Default")
      (node (ref "C64") (pin "2") (pinfunction "2_2") (pintype "passive"))
      (node (ref "L1") (pin "2") (pinfunction "2_2") (pintype "passive"))
      (node (ref "R53") (pin "1") (pinfunction "1_1") (pintype "passive"))
      (node (ref "R55") (pin "2") (pinfunction "2_2") (pintype "passive"))
    )
    (net (code "31") (name "Net-(C67-Pad1)") (class "Default")
      (node (ref "C67") (pin "1") (pinfunction "1_1") (pintype "passive"))
      (node (ref "C68") (pin "1") (pinfunction "1_1") (pintype "passive"))
      (node (ref "C69") (pin "2") (pinfunction "2_2") (pintype "passive"))
      (node (ref "R58") (pin "2") (pinfunction "2_2") (pintype "passive"))
      (node (ref "R63") (pin "2") (pinfunction "2_2") (pintype "passive"))
    )
    (net (code "32") (name "Net-(C69-Pad1)") (class "Default")
      (node (ref "C69") (pin "1") (pinfunction "1_1") (pintype "passive"))
      (node (ref "R59") (pin "2") (pinfunction "2_2") (pintype "passive"))
      (node (ref "R63") (pin "1") (pinfunction "1_1") (pintype "passive"))
    )
    (net (code "33") (name "Net-(C74-Pad2)") (class "Default")
      (node (ref "C74") (pin "2") (pinfunction "2_2") (pintype "passive"))
      (node (ref "C75") (pin "1") (pinfunction "1_1") (pintype "passive"))
      (node (ref "C76") (pin "1") (pinfunction "1_1") (pintype "passive"))
      (node (ref "R67") (pin "2") (pinfunction "2_2") (pintype "passive"))
      (node (ref "R69") (pin "1") (pinfunction "1_1") (pintype "passive"))
    )
    (net (code "34") (name "Net-(C75-Pad2)") (class "Default")
      (node (ref "C75") (pin "2") (pinfunction "2_2") (pintype "passive"))
      (node (ref "R69") (pin "2") (pinfunction "2_2") (pintype "passive"))
      (node (ref "R70") (pin "1") (pinfunction "1_1") (pintype "passive"))
    )
    (net (code "35") (name "Net-(C78-Pad1)") (class "Default")
      (node (ref "C78") (pin "1") (pinfunction "1_1") (pintype "passive"))
      (node (ref "L2") (pin "1") (pinfunction "1_1") (pintype "passive"))
      (node (ref "R72") (pin "1") (pinfunction "1_1") (pintype "passive"))
      (node (ref "R74") (pin "1") (pinfunction "1_1") (pintype "passive"))
    )
    (net (code "36") (name "Net-(J7-Pad2)") (class "Default")
      (node (ref "J7") (pin "2") (pinfunction "2_2") (pintype "passive"))
      (node (ref "L1") (pin "1") (pinfunction "1_1") (pintype "passive"))
    )
    (net (code "37") (name "Net-(J8-Pad2)") (class "Default")
      (node (ref "J8") (pin "2") (pinfunction "2_2") (pintype "passive"))
      (node (ref "L2") (pin "2") (pinfunction "2_2") (pintype "passive"))
    )
    (net (code "38") (name "Net-(R57-Pad2)") (class "Default")
      (node (ref "R57") (pin "2") (pinfunction "2_2") (pintype "passive"))
      (node (ref "R58") (pin "1") (pinfunction "1_1") (pintype "passive"))
    )
    (net (code "39") (name "Net-(R66-Pad2)") (class "Default")
      (node (ref "R66") (pin "2") (pinfunction "2_2") (pintype "passive"))
      (node (ref "R67") (pin "1") (pinfunction "1_1") (pintype "passive"))
    )
    (net (code "40") (name "Net-(SW1A-COM)") (class "Default")
      (node (ref "C28") (pin "2") (pinfunction "2_2") (pintype "passive"))
      (node (ref "R1") (pin "3") (pinfunction "3_3") (pintype "passive"))
      (node (ref "R14") (pin "2") (pinfunction "2_2") (pintype "passive"))
      (node (ref "R35") (pin "2") (pinfunction "2_2") (pintype "passive"))
      (node (ref "SW1") (pin "2") (pinfunction "COM_2") (pintype "passive"))
      (node (ref "SW1") (pin "3") (pinfunction "UP_3") (pintype "passive"))
      (node (ref "U5") (pin "1") (pinfunction "OUT_A_1") (pintype "passive"))
    )
    (net (code "41") (name "Net-(SW1A-DOWN)") (class "Default")
      (node (ref "R75") (pin "1") (pinfunction "1_1") (pintype "passive"))
      (node (ref "SW1") (pin "1") (pinfunction "DOWN_1") (pintype "passive"))
    )
    (net (code "42") (name "Net-(SW1B-COM)") (class "Default")
      (node (ref "C42") (pin "2") (pinfunction "2_2") (pintype "passive"))
      (node (ref "R1") (pin "6") (pinfunction "6_6") (pintype "passive"))
      (node (ref "R21") (pin "2") (pinfunction "2_2") (pintype "passive"))
      (node (ref "R60") (pin "2") (pinfunction "2_2") (pintype "passive"))
      (node (ref "SW1") (pin "5") (pinfunction "COM_5") (pintype "passive"))
      (node (ref "SW1") (pin "6") (pinfunction "UP_6") (pintype "passive"))
      (node (ref "U5") (pin "8") (pinfunction "OUT_C_8") (pintype "passive"))
    )
    (net (code "43") (name "Net-(SW1B-DOWN)") (class "Default")
      (node (ref "R76") (pin "1") (pinfunction "1_1") (pintype "passive"))
      (node (ref "SW1") (pin "4") (pinfunction "DOWN_4") (pintype "passive"))
    )
    (net (code "44") (name "Net-(SW5A-COM)") (class "Default")
      (node (ref "R62") (pin "1") (pinfunction "1_1") (pintype "passive"))
      (node (ref "SW5") (pin "2") (pinfunction "COM_2") (pintype "passive"))
      (node (ref "SW5") (pin "3") (pinfunction "UP_3") (pintype "passive"))
    )
    (net (code "45") (name "Net-(SW5B-COM)") (class "Default")
      (node (ref "R68") (pin "2") (pinfunction "2_2") (pintype "passive"))
      (node (ref "SW5") (pin "5") (pinfunction "COM_5") (pintype "passive"))
      (node (ref "SW5") (pin "6") (pinfunction "UP_6") (pintype "passive"))
    )
    (net (code "46") (name "Net-(U1A-+IN_A)") (class "Default")
      (node (ref "C1") (pin "2") (pinfunction "2_2") (pintype "passive"))
      (node (ref "R3") (pin "2") (pinfunction "2_2") (pintype "passive"))
      (node (ref "U1") (pin "3") (pinfunction "+IN_A_3") (pintype "passive"))
    )
    (net (code "47") (name "Net-(U1A--IN_A)") (class "Default")
      (node (ref "R2") (pin "1") (pinfunction "1_1") (pintype "passive"))
      (node (ref "U1") (pin "1") (pinfunction "OUT_A_1") (pintype "passive"))
      (node (ref "U1") (pin "2") (pinfunction "-IN_A_2") (pintype "passive"))
    )
    (net (code "48") (name "Net-(U1B-IN_B-)") (class "Default")
      (node (ref "C11") (pin "1") (pinfunction "1_1") (pintype "passive"))
      (node (ref "R10") (pin "1") (pinfunction "1_1") (pintype "passive"))
      (node (ref "R8") (pin "2") (pinfunction "2_2") (pintype "passive"))
      (node (ref "U1") (pin "6") (pinfunction "IN_B-_6") (pintype "passive"))
    )
    (net (code "49") (name "Net-(U1B-OUT_B)") (class "Default")
      (node (ref "C11") (pin "2") (pinfunction "2_2") (pintype "passive"))
      (node (ref "R10") (pin "2") (pinfunction "2_2") (pintype "passive"))
      (node (ref "R149") (pin "1") (pinfunction "1_1") (pintype "passive"))
      (node (ref "R184") (pin "1") (pinfunction "1_1") (pintype "passive"))
      (node (ref "U1") (pin "7") (pinfunction "OUT_B_7") (pintype "passive"))
    )
    (net (code "50") (name "Net-(U1C-IN_C+)") (class "Default")
      (node (ref "C10") (pin "2") (pinfunction "2_2") (pintype "passive"))
      (node (ref "R9") (pin "2") (pinfunction "2_2") (pintype "passive"))
      (node (ref "U1") (pin "10") (pinfunction "IN_C+_10") (pintype "passive"))
    )
    (net (code "51") (name "Net-(U1C-IN_C-)") (class "Default")
      (node (ref "R8") (pin "1") (pinfunction "1_1") (pintype "passive"))
      (node (ref "U1") (pin "8") (pinfunction "OUT_C_8") (pintype "passive"))
      (node (ref "U1") (pin "9") (pinfunction "IN_C-_9") (pintype "passive"))
    )
    (net (code "52") (name "Net-(U1D-IN_D-)") (class "Default")
      (node (ref "C2") (pin "1") (pinfunction "1_1") (pintype "passive"))
      (node (ref "R2") (pin "2") (pinfunction "2_2") (pintype "passive"))
      (node (ref "R4") (pin "1") (pinfunction "1_1") (pintype "passive"))
      (node (ref "U1") (pin "13") (pinfunction "IN_D-_13") (pintype "passive"))
    )
    (net (code "53") (name "Net-(U1D-OUT_D)") (class "Default")
      (node (ref "C2") (pin "2") (pinfunction "2_2") (pintype "passive"))
      (node (ref "R148") (pin "1") (pinfunction "1_1") (pintype "passive"))
      (node (ref "R173") (pin "1") (pinfunction "1_1") (pintype "passive"))
      (node (ref "R4") (pin "2") (pinfunction "2_2") (pintype "passive"))
      (node (ref "U1") (pin "14") (pinfunction "OUT_D_14") (pintype "passive"))
    )
    (net (code "54") (name "Net-(U2A-+IN_A)") (class "Default")
      (node (ref "C13") (pin "2") (pinfunction "2_2") (pintype "passive"))
      (node (ref "R12") (pin "2") (pinfunction "2_2") (pintype "passive"))
      (node (ref "U2") (pin "3") (pinfunction "+IN_A_3") (pintype "passive"))
    )
    (net (code "55") (name "Net-(U2A--IN_A)") (class "Default")
      (node (ref "R11") (pin "1") (pinfunction "1_1") (pintype "passive"))
      (node (ref "U2") (pin "1") (pinfunction "OUT_A_1") (pintype "passive"))
      (node (ref "U2") (pin "2") (pinfunction "-IN_A_2") (pintype "passive"))
    )
    (net (code "56") (name "Net-(U2B-IN_B-)") (class "Default")
      (node (ref "C19") (pin "1") (pinfunction "1_1") (pintype "passive"))
      (node (ref "R22") (pin "2") (pinfunction "2_2") (pintype "passive"))
      (node (ref "R24") (pin "1") (pinfunction "1_1") (pintype "passive"))
      (node (ref "U2") (pin "6") (pinfunction "IN_B-_6") (pintype "passive"))
    )
    (net (code "57") (name "Net-(U2B-OUT_B)") (class "Default")
      (node (ref "C19") (pin "2") (pinfunction "2_2") (pintype "passive"))
      (node (ref "R151") (pin "1") (pinfunction "1_1") (pintype "passive"))
      (node (ref "R20") (pin "1") (pinfunction "1_1") (pintype "passive"))
      (node (ref "R24") (pin "2") (pinfunction "2_2") (pintype "passive"))
      (node (ref "U2") (pin "7") (pinfunction "OUT_B_7") (pintype "passive"))
    )
    (net (code "58") (name "Net-(U2C-IN_C+)") (class "Default")
      (node (ref "C18") (pin "2") (pinfunction "2_2") (pintype "passive"))
      (node (ref "R23") (pin "2") (pinfunction "2_2") (pintype "passive"))
      (node (ref "U2") (pin "10") (pinfunction "IN_C+_10") (pintype "passive"))
    )
    (net (code "59") (name "Net-(U2C-IN_C-)") (class "Default")
      (node (ref "R22") (pin "1") (pinfunction "1_1") (pintype "passive"))
      (node (ref "U2") (pin "8") (pinfunction "OUT_C_8") (pintype "passive"))
      (node (ref "U2") (pin "9") (pinfunction "IN_C-_9") (pintype "passive"))
    )
    (net (code "60") (name "Net-(U2D-IN_D-)") (class "Default")
      (node (ref "C16") (pin "1") (pinfunction "1_1") (pintype "passive"))
      (node (ref "R11") (pin "2") (pinfunction "2_2") (pintype "passive"))
      (node (ref "R17") (pin "1") (pinfunction "1_1") (pintype "passive"))
      (node (ref "U2") (pin "13") (pinfunction "IN_D-_13") (pintype "passive"))
    )
    (net (code "61") (name "Net-(U2D-OUT_D)") (class "Default")
      (node (ref "C16") (pin "2") (pinfunction "2_2") (pintype "passive"))
      (node (ref "R150") (pin "1") (pinfunction "1_1") (pintype "passive"))
      (node (ref "R17") (pin "2") (pinfunction "2_2") (pintype "passive"))
      (node (ref "R200") (pin "1") (pinfunction "1_1") (pintype "passive"))
      (node (ref "U2") (pin "14") (pinfunction "OUT_D_14") (pintype "passive"))
    )
    (net (code "62") (name "Net-(U3A--IN_A)") (class "Default")
      (node (ref "C21") (pin "1") (pinfunction "1_1") (pintype "passive"))
      (node (ref "R28") (pin "2") (pinfunction "2_2") (pintype "passive"))
      (node (ref "R34") (pin "1") (pinfunction "1_1") (pintype "passive"))
      (node (ref "U3") (pin "2") (pinfunction "-IN_A_2") (pintype "passive"))
    )
    (net (code "63") (name "Net-(U3A-OUT_A)") (class "Default")
      (node (ref "C21") (pin "2") (pinfunction "2_2") (pintype "passive"))
      (node (ref "R148") (pin "4") (pinfunction "4_4") (pintype "passive"))
      (node (ref "R177") (pin "1") (pinfunction "1_1") (pintype "passive"))
      (node (ref "R34") (pin "2") (pinfunction "2_2") (pintype "passive"))
      (node (ref "U3") (pin "1") (pinfunction "OUT_A_1") (pintype "passive"))
    )
    (net (code "64") (name "Net-(U3B-IN_B+)") (class "Default")
      (node (ref "C25") (pin "2") (pinfunction "2_2") (pintype "passive"))
      (node (ref "R39") (pin "2") (pinfunction "2_2") (pintype "passive"))
      (node (ref "U3") (pin "5") (pinfunction "IN_B+_5") (pintype "passive"))
    )
    (net (code "65") (name "Net-(U3B-IN_B-)") (class "Default")
      (node (ref "R38") (pin "1") (pinfunction "1_1") (pintype "passive"))
      (node (ref "U3") (pin "6") (pinfunction "IN_B-_6") (pintype "passive"))
      (node (ref "U3") (pin "7") (pinfunction "OUT_B_7") (pintype "passive"))
    )
    (net (code "66") (name "Net-(U3C-IN_C-)") (class "Default")
      (node (ref "C27") (pin "1") (pinfunction "1_1") (pintype "passive"))
      (node (ref "R38") (pin "2") (pinfunction "2_2") (pintype "passive"))
      (node (ref "R40") (pin "1") (pinfunction "1_1") (pintype "passive"))
      (node (ref "U3") (pin "9") (pinfunction "IN_C-_9") (pintype "passive"))
    )
    (net (code "67") (name "Net-(U3C-OUT_C)") (class "Default")
      (node (ref "C27") (pin "2") (pinfunction "2_2") (pintype "passive"))
      (node (ref "R149") (pin "4") (pinfunction "4_4") (pintype "passive"))
      (node (ref "R187") (pin "1") (pinfunction "1_1") (pintype "passive"))
      (node (ref "R40") (pin "2") (pinfunction "2_2") (pintype "passive"))
      (node (ref "U3") (pin "8") (pinfunction "OUT_C_8") (pintype "passive"))
    )
    (net (code "68") (name "Net-(U3D-IN_D+)") (class "Default")
      (node (ref "C20") (pin "2") (pinfunction "2_2") (pintype "passive"))
      (node (ref "R33") (pin "2") (pinfunction "2_2") (pintype "passive"))
      (node (ref "U3") (pin "12") (pinfunction "IN_D+_12") (pintype "passive"))
    )
    (net (code "69") (name "Net-(U3D-IN_D-)") (class "Default")
      (node (ref "R28") (pin "1") (pinfunction "1_1") (pintype "passive"))
      (node (ref "U3") (pin "13") (pinfunction "IN_D-_13") (pintype "passive"))
      (node (ref "U3") (pin "14") (pinfunction "OUT_D_14") (pintype "passive"))
    )
    (net (code "70") (name "Net-(U4A--IN_A)") (class "Default")
      (node (ref "C32") (pin "1") (pinfunction "1_1") (pintype "passive"))
      (node (ref "R41") (pin "2") (pinfunction "2_2") (pintype "passive"))
      (node (ref "R43") (pin "1") (pinfunction "1_1") (pintype "passive"))
      (node (ref "U4") (pin "2") (pinfunction "-IN_A_2") (pintype "passive"))
    )
    (net (code "71") (name "Net-(U4A-OUT_A)") (class "Default")
      (node (ref "C32") (pin "2") (pinfunction "2_2") (pintype "passive"))
      (node (ref "R150") (pin "4") (pinfunction "4_4") (pintype "passive"))
      (node (ref "R201") (pin "1") (pinfunction "1_1") (pintype "passive"))
      (node (ref "R43") (pin "2") (pinfunction "2_2") (pintype "passive"))
      (node (ref "U4") (pin "1") (pinfunction "OUT_A_1") (pintype "passive"))
    )
    (net (code "72") (name "Net-(U4B-IN_B+)") (class "Default")
      (node (ref "C34") (pin "2") (pinfunction "2_2") (pintype "passive"))
      (node (ref "R45") (pin "2") (pinfunction "2_2") (pintype "passive"))
      (node (ref "U4") (pin "5") (pinfunction "IN_B+_5") (pintype "passive"))
    )
    (net (code "73") (name "Net-(U4B-IN_B-)") (class "Default")
      (node (ref "R44") (pin "1") (pinfunction "1_1") (pintype "passive"))
      (node (ref "U4") (pin "6") (pinfunction "IN_B-_6") (pintype "passive"))
      (node (ref "U4") (pin "7") (pinfunction "OUT_B_7") (pintype "passive"))
    )
    (net (code "74") (name "Net-(U4C-IN_C-)") (class "Default")
      (node (ref "C35") (pin "1") (pinfunction "1_1") (pintype "passive"))
      (node (ref "R44") (pin "2") (pinfunction "2_2") (pintype "passive"))
      (node (ref "R46") (pin "1") (pinfunction "1_1") (pintype "passive"))
      (node (ref "U4") (pin "9") (pinfunction "IN_C-_9") (pintype "passive"))
    )
    (net (code "75") (name "Net-(U4C-OUT_C)") (class "Default")
      (node (ref "C35") (pin "2") (pinfunction "2_2") (pintype "passive"))
      (node (ref "R151") (pin "4") (pinfunction "4_4") (pintype "passive"))
      (node (ref "R207") (pin "1") (pinfunction "1_1") (pintype "passive"))
      (node (ref "R46") (pin "2") (pinfunction "2_2") (pintype "passive"))
      (node (ref "U4") (pin "8") (pinfunction "OUT_C_8") (pintype "passive"))
    )
    (net (code "76") (name "Net-(U4D-IN_D+)") (class "Default")
      (node (ref "C29") (pin "2") (pinfunction "2_2") (pintype "passive"))
      (node (ref "R42") (pin "2") (pinfunction "2_2") (pintype "passive"))
      (node (ref "U4") (pin "12") (pinfunction "IN_D+_12") (pintype "passive"))
    )
    (net (code "77") (name "Net-(U4D-IN_D-)") (class "Default")
      (node (ref "R41") (pin "1") (pinfunction "1_1") (pintype "passive"))
      (node (ref "U4") (pin "13") (pinfunction "IN_D-_13") (pintype "passive"))
      (node (ref "U4") (pin "14") (pinfunction "OUT_D_14") (pintype "passive"))
    )
    (net (code "78") (name "Net-(U5A--IN_A)") (class "Default")
      (node (ref "C28") (pin "1") (pinfunction "1_1") (pintype "passive"))
      (node (ref "R14") (pin "1") (pinfunction "1_1") (pintype "passive"))
      (node (ref "R173") (pin "2") (pinfunction "2_2") (pintype "passive"))
      (node (ref "R184") (pin "2") (pinfunction "2_2") (pintype "passive"))
      (node (ref "R20") (pin "2") (pinfunction "2_2") (pintype "passive"))
      (node (ref "R200") (pin "2") (pinfunction "2_2") (pintype "passive"))
      (node (ref "U5") (pin "2") (pinfunction "-IN_A_2") (pintype "passive"))
    )
    (net (code "79") (name "Net-(U5B-IN_B+)") (class "Default")
      (node (ref "C14") (pin "2") (pinfunction "2_2") (pintype "passive"))
      (node (ref "R19") (pin "2") (pinfunction "2_2") (pintype "passive"))
      (node (ref "U5") (pin "5") (pinfunction "IN_B+_5") (pintype "passive"))
    )
    (net (code "80") (name "Net-(U5B-IN_B-)") (class "Default")
      (node (ref "R15") (pin "1") (pinfunction "1_1") (pintype "passive"))
      (node (ref "U5") (pin "6") (pinfunction "IN_B-_6") (pintype "passive"))
      (node (ref "U5") (pin "7") (pinfunction "OUT_B_7") (pintype "passive"))
    )
    (net (code "81") (name "Net-(U5C-IN_C-)") (class "Default")
      (node (ref "C42") (pin "1") (pinfunction "1_1") (pintype "passive"))
      (node (ref "R177") (pin "2") (pinfunction "2_2") (pintype "passive"))
      (node (ref "R187") (pin "2") (pinfunction "2_2") (pintype "passive"))
      (node (ref "R201") (pin "2") (pinfunction "2_2") (pintype "passive"))
      (node (ref "R207") (pin "2") (pinfunction "2_2") (pintype "passive"))
      (node (ref "R21") (pin "1") (pinfunction "1_1") (pintype "passive"))
      (node (ref "U5") (pin "9") (pinfunction "IN_C-_9") (pintype "passive"))
    )
    (net (code "82") (name "Net-(U5D-IN_D+)") (class "Default")
      (node (ref "C22") (pin "2") (pinfunction "2_2") (pintype "passive"))
      (node (ref "R37") (pin "2") (pinfunction "2_2") (pintype "passive"))
      (node (ref "U5") (pin "12") (pinfunction "IN_D+_12") (pintype "passive"))
    )
    (net (code "83") (name "Net-(U5D-IN_D-)") (class "Default")
      (node (ref "R36") (pin "1") (pinfunction "1_1") (pintype "passive"))
      (node (ref "U5") (pin "13") (pinfunction "IN_D-_13") (pintype "passive"))
      (node (ref "U5") (pin "14") (pinfunction "OUT_D_14") (pintype "passive"))
    )
    (net (code "84") (name "Net-(U20A-+IN_A)") (class "Default")
      (node (ref "C80") (pin "1") (pinfunction "1_1") (pintype "passive"))
      (node (ref "R74") (pin "2") (pinfunction "2_2") (pintype "passive"))
      (node (ref "U20") (pin "3") (pinfunction "+IN_A_3") (pintype "passive"))
    )
    (net (code "85") (name "Net-(U20A--IN_A)") (class "Default")
      (node (ref "C74") (pin "1") (pinfunction "1_1") (pintype "passive"))
      (node (ref "C76") (pin "2") (pinfunction "2_2") (pintype "passive"))
      (node (ref "R66") (pin "1") (pinfunction "1_1") (pintype "passive"))
      (node (ref "R68") (pin "1") (pinfunction "1_1") (pintype "passive"))
      (node (ref "U20") (pin "2") (pinfunction "-IN_A_2") (pintype "passive"))
    )
    (net (code "86") (name "Net-(U20A-OUT_A)") (class "Default")
      (node (ref "C79") (pin "1") (pinfunction "1_1") (pintype "passive"))
      (node (ref "R70") (pin "2") (pinfunction "2_2") (pintype "passive"))
      (node (ref "U20") (pin "1") (pinfunction "OUT_A_1") (pintype "passive"))
    )
    (net (code "87") (name "Net-(U20B-IN_B+)") (class "Default")
      (node (ref "C63") (pin "2") (pinfunction "2_2") (pintype "passive"))
      (node (ref "R53") (pin "2") (pinfunction "2_2") (pintype "passive"))
      (node (ref "U20") (pin "5") (pinfunction "IN_B+_5") (pintype "passive"))
    )
    (net (code "88") (name "Net-(U20B-IN_B-)") (class "Default")
      (node (ref "C67") (pin "2") (pinfunction "2_2") (pintype "passive"))
      (node (ref "C68") (pin "2") (pinfunction "2_2") (pintype "passive"))
      (node (ref "R57") (pin "1") (pinfunction "1_1") (pintype "passive"))
      (node (ref "R62") (pin "2") (pinfunction "2_2") (pintype "passive"))
      (node (ref "U20") (pin "6") (pinfunction "IN_B-_6") (pintype "passive"))
    )
    (net (code "89") (name "Net-(U20B-OUT_B)") (class "Default")
      (node (ref "C65") (pin "1") (pinfunction "1_1") (pintype "passive"))
      (node (ref "R59") (pin "1") (pinfunction "1_1") (pintype "passive"))
      (node (ref "U20") (pin "7") (pinfunction "OUT_B_7") (pintype "passive"))
    )
  )
)
